# THzChipCarrierBoard.net
KiCad netlist of a schematic drawn in EAGLE
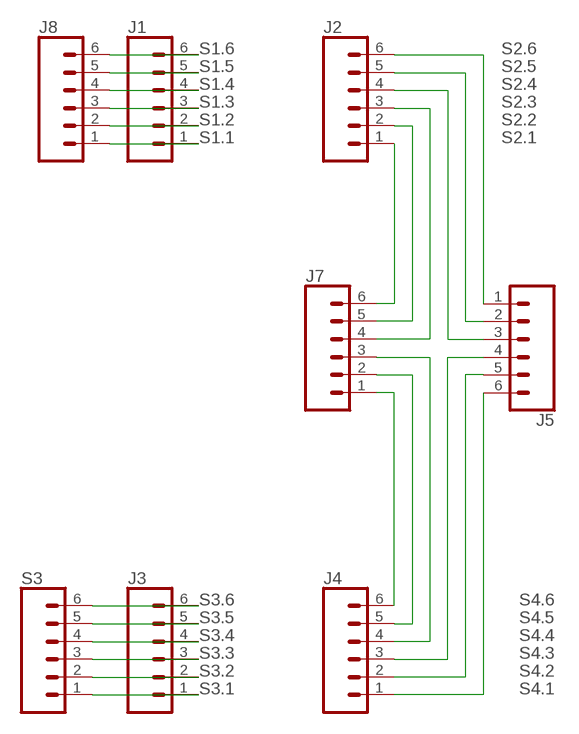
[diagram p0: schematic, sheet 1]

(export (version "E")
  (design (tool "Eeschema 10.0.6"))
  (components
    (comp (ref "J1")
      (value "CONN_06SILK_FEMALE_PTH")
      (footprint "eagle-import:1X06")
      (libsource (lib "eagle-import") (part "CONN_06SILK_FEMALE_PTH"))
    )
    (comp (ref "J2")
      (value "CONN_06SILK_FEMALE_PTH")
      (footprint "eagle-import:1X06")
      (libsource (lib "eagle-import") (part "CONN_06SILK_FEMALE_PTH"))
    )
    (comp (ref "J3")
      (value "CONN_06SILK_FEMALE_PTH")
      (footprint "eagle-import:1X06")
      (libsource (lib "eagle-import") (part "CONN_06SILK_FEMALE_PTH"))
    )
    (comp (ref "J4")
      (value "CONN_06SILK_FEMALE_PTH")
      (footprint "eagle-import:1X06")
      (libsource (lib "eagle-import") (part "CONN_06SILK_FEMALE_PTH"))
    )
    (comp (ref "J5")
      (value "CONN_06SILK_FEMALE_PTH")
      (footprint "eagle-import:1X06")
      (libsource (lib "eagle-import") (part "CONN_06SILK_FEMALE_PTH"))
    )
    (comp (ref "J7")
      (value "CONN_06SILK_FEMALE_PTH")
      (footprint "eagle-import:1X06")
      (libsource (lib "eagle-import") (part "CONN_06SILK_FEMALE_PTH"))
    )
    (comp (ref "J8")
      (value "CONN_06SILK_FEMALE_PTH")
      (footprint "eagle-import:1X06")
      (libsource (lib "eagle-import") (part "CONN_06SILK_FEMALE_PTH"))
    )
    (comp (ref "S3")
      (value "CONN_06SILK_FEMALE_PTH")
      (footprint "eagle-import:1X06")
      (libsource (lib "eagle-import") (part "CONN_06SILK_FEMALE_PTH"))
    )
  )
  (nets
    (net (code "1") (name "/S1.1") (class "Default")
      (node (ref "J1") (pin "1") (pinfunction "1_1") (pintype "passive"))
      (node (ref "J8") (pin "1") (pinfunction "1_1") (pintype "passive"))
    )
    (net (code "2") (name "/S1.2") (class "Default")
      (node (ref "J1") (pin "2") (pinfunction "2_2") (pintype "passive"))
      (node (ref "J8") (pin "2") (pinfunction "2_2") (pintype "passive"))
    )
    (net (code "3") (name "/S1.3") (class "Default")
      (node (ref "J1") (pin "3") (pinfunction "3_3") (pintype "passive"))
      (node (ref "J8") (pin "3") (pinfunction "3_3") (pintype "passive"))
    )
    (net (code "4") (name "/S1.4") (class "Default")
      (node (ref "J1") (pin "4") (pinfunction "4_4") (pintype "passive"))
      (node (ref "J8") (pin "4") (pinfunction "4_4") (pintype "passive"))
    )
    (net (code "5") (name "/S1.5") (class "Default")
      (node (ref "J1") (pin "5") (pinfunction "5_5") (pintype "passive"))
      (node (ref "J8") (pin "5") (pinfunction "5_5") (pintype "passive"))
    )
    (net (code "6") (name "/S1.6") (class "Default")
      (node (ref "J1") (pin "6") (pinfunction "6_6") (pintype "passive"))
      (node (ref "J8") (pin "6") (pinfunction "6_6") (pintype "passive"))
    )
    (net (code "7") (name "/S2.1") (class "Default")
      (node (ref "J2") (pin "1") (pinfunction "1_1") (pintype "passive"))
      (node (ref "J7") (pin "6") (pinfunction "6_6") (pintype "passive"))
    )
    (net (code "8") (name "/S2.2") (class "Default")
      (node (ref "J2") (pin "2") (pinfunction "2_2") (pintype "passive"))
      (node (ref "J7") (pin "5") (pinfunction "5_5") (pintype "passive"))
    )
    (net (code "9") (name "/S2.3") (class "Default")
      (node (ref "J2") (pin "3") (pinfunction "3_3") (pintype "passive"))
      (node (ref "J7") (pin "4") (pinfunction "4_4") (pintype "passive"))
    )
    (net (code "10") (name "/S2.4") (class "Default")
      (node (ref "J2") (pin "4") (pinfunction "4_4") (pintype "passive"))
      (node (ref "J5") (pin "3") (pinfunction "3_3") (pintype "passive"))
    )
    (net (code "11") (name "/S2.5") (class "Default")
      (node (ref "J2") (pin "5") (pinfunction "5_5") (pintype "passive"))
      (node (ref "J5") (pin "2") (pinfunction "2_2") (pintype "passive"))
    )
    (net (code "12") (name "/S2.6") (class "Default")
      (node (ref "J2") (pin "6") (pinfunction "6_6") (pintype "passive"))
      (node (ref "J5") (pin "1") (pinfunction "1_1") (pintype "passive"))
    )
    (net (code "13") (name "/S3.1") (class "Default")
      (node (ref "J3") (pin "1") (pinfunction "1_1") (pintype "passive"))
      (node (ref "S3") (pin "1") (pinfunction "1_1") (pintype "passive"))
    )
    (net (code "14") (name "/S3.2") (class "Default")
      (node (ref "J3") (pin "2") (pinfunction "2_2") (pintype "passive"))
      (node (ref "S3") (pin "2") (pinfunction "2_2") (pintype "passive"))
    )
    (net (code "15") (name "/S3.3") (class "Default")
      (node (ref "J3") (pin "3") (pinfunction "3_3") (pintype "passive"))
      (node (ref "S3") (pin "3") (pinfunction "3_3") (pintype "passive"))
    )
    (net (code "16") (name "/S3.4") (class "Default")
      (node (ref "J3") (pin "4") (pinfunction "4_4") (pintype "passive"))
      (node (ref "S3") (pin "4") (pinfunction "4_4") (pintype "passive"))
    )
    (net (code "17") (name "/S3.5") (class "Default")
      (node (ref "J3") (pin "5") (pinfunction "5_5") (pintype "passive"))
      (node (ref "S3") (pin "5") (pinfunction "5_5") (pintype "passive"))
    )
    (net (code "18") (name "/S3.6") (class "Default")
      (node (ref "J3") (pin "6") (pinfunction "6_6") (pintype "passive"))
      (node (ref "S3") (pin "6") (pinfunction "6_6") (pintype "passive"))
    )
    (net (code "19") (name "/S4.1") (class "Default")
      (node (ref "J4") (pin "1") (pinfunction "1_1") (pintype "passive"))
      (node (ref "J5") (pin "6") (pinfunction "6_6") (pintype "passive"))
    )
    (net (code "20") (name "/S4.2") (class "Default")
      (node (ref "J4") (pin "2") (pinfunction "2_2") (pintype "passive"))
      (node (ref "J5") (pin "5") (pinfunction "5_5") (pintype "passive"))
    )
    (net (code "21") (name "/S4.3") (class "Default")
      (node (ref "J4") (pin "3") (pinfunction "3_3") (pintype "passive"))
      (node (ref "J5") (pin "4") (pinfunction "4_4") (pintype "passive"))
    )
    (net (code "22") (name "/S4.4") (class "Default")
      (node (ref "J4") (pin "4") (pinfunction "4_4") (pintype "passive"))
      (node (ref "J7") (pin "3") (pinfunction "3_3") (pintype "passive"))
    )
    (net (code "23") (name "/S4.5") (class "Default")
      (node (ref "J4") (pin "5") (pinfunction "5_5") (pintype "passive"))
      (node (ref "J7") (pin "2") (pinfunction "2_2") (pintype "passive"))
    )
    (net (code "24") (name "/S4.6") (class "Default")
      (node (ref "J4") (pin "6") (pinfunction "6_6") (pintype "passive"))
      (node (ref "J7") (pin "1") (pinfunction "1_1") (pintype "passive"))
    )
  )
)
